# FM_Radio_Simple_Receiver.net
KiCad netlist of a schematic drawn in EAGLE
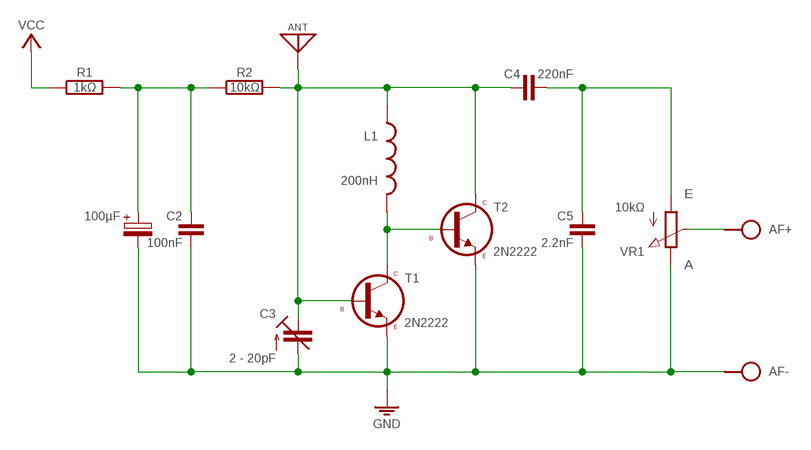
[diagram p0: schematic, sheet 1]

(export (version "E")
  (design (tool "Eeschema 10.0.6"))
  (components
    (comp (ref "100µF")
      (value "CPOLE2,5-5/V")
      (footprint "eagle-import:E2,5-5_V")
      (libsource (lib "eagle-import") (part "CPOLE2,5-5/V"))
    )
    (comp (ref "AF")
      (value "SPAD+-+-")
      (footprint "eagle-import:SPAD+-")
      (libsource (lib "eagle-import") (part "SPAD+-+-"))
    )
    (comp (ref "ANT")
      (value "ANT")
      (footprint "eagle-import:SPAD")
      (libsource (lib "eagle-import") (part "ANT"))
    )
    (comp (ref "BAT")
      (value "VCC_GNDL")
      (footprint "eagle-import:SPAD-+")
      (libsource (lib "eagle-import") (part "VCC_GNDL"))
    )
    (comp (ref "C2")
      (value "100nF")
      (footprint "eagle-import:C050-020X036_V")
      (libsource (lib "eagle-import") (part "C050-020X036/V"))
    )
    (comp (ref "C3")
      (value "2 - 20pF")
      (footprint "eagle-import:TRIM-2222-808")
      (libsource (lib "eagle-import") (part "C-TR-PH20127"))
    )
    (comp (ref "C4")
      (value "220nF")
      (footprint "eagle-import:C050-020X044")
      (libsource (lib "eagle-import") (part "C-H050-020X044"))
    )
    (comp (ref "C5")
      (value "2.2nF")
      (footprint "eagle-import:C050-020X036_V")
      (libsource (lib "eagle-import") (part "C050-020X036/V"))
    )
    (comp (ref "L1")
      (value "200nH")
      (footprint "eagle-import:L-04_7-V")
      (libsource (lib "eagle-import") (part "L04/7-V"))
    )
    (comp (ref "R1")
      (value "1kΩ")
      (footprint "eagle-import:0204_10")
      (libsource (lib "eagle-import") (part "R-H0204/10"))
    )
    (comp (ref "R2")
      (value "10kΩ")
      (footprint "eagle-import:0204_10")
      (libsource (lib "eagle-import") (part "R-H0204/10"))
    )
    (comp (ref "T1")
      (value "2N2222")
      (footprint "eagle-import:TO92-EBC")
      (libsource (lib "eagle-import") (part "2N2222"))
    )
    (comp (ref "T2")
      (value "2N2222")
      (footprint "eagle-import:TO92-EBC")
      (libsource (lib "eagle-import") (part "2N2222"))
    )
    (comp (ref "VR1")
      (value "10kΩ")
      (footprint "eagle-import:POT")
      (libsource (lib "eagle-import") (part "POT"))
    )
  )
  (nets
    (net (code "1") (name "Net-(100µF-Pad+)") (class "Default")
      (node (ref "100µF") (pin "+") (pinfunction "+_+") (pintype "passive"))
      (node (ref "C2") (pin "1") (pinfunction "1_1") (pintype "passive"))
      (node (ref "R1") (pin "2") (pinfunction "2_2") (pintype "passive"))
      (node (ref "R2") (pin "1") (pinfunction "1_1") (pintype "passive"))
    )
    (net (code "2") (name "Net-(AFA-P$1)") (class "Default")
      (node (ref "AF") (pin "2") (pinfunction "P$1_2") (pintype "passive"))
      (node (ref "VR1") (pin "S") (pinfunction "S_S") (pintype "passive"))
    )
    (net (code "3") (name "Net-(AFB-P$1)") (class "Default")
      (node (ref "100µF") (pin "-") (pinfunction "-_-") (pintype "passive"))
      (node (ref "AF") (pin "1") (pinfunction "P$1_1") (pintype "passive"))
      (node (ref "BAT") (pin "1") (pinfunction "GND_1") (pintype "power_in"))
      (node (ref "C2") (pin "2") (pinfunction "2_2") (pintype "passive"))
      (node (ref "C3") (pin "1") (pinfunction "A_1") (pintype "passive"))
      (node (ref "C3") (pin "3") (pinfunction "A_3") (pintype "passive"))
      (node (ref "C5") (pin "2") (pinfunction "2_2") (pintype "passive"))
      (node (ref "T1") (pin "E") (pinfunction "E_E") (pintype "passive"))
      (node (ref "T2") (pin "E") (pinfunction "E_E") (pintype "passive"))
      (node (ref "VR1") (pin "E") (pinfunction "E_E") (pintype "passive"))
    )
    (net (code "4") (name "Net-(BATA-VCC)") (class "Default")
      (node (ref "BAT") (pin "2") (pinfunction "VCC_2") (pintype "power_in"))
      (node (ref "R1") (pin "1") (pinfunction "1_1") (pintype "passive"))
    )
    (net (code "5") (name "Net-(C3-E)") (class "Default")
      (node (ref "ANT") (pin "1") (pinfunction "1_1") (pintype "output"))
      (node (ref "C3") (pin "2") (pinfunction "E_2") (pintype "passive"))
      (node (ref "C4") (pin "1") (pinfunction "1_1") (pintype "passive"))
      (node (ref "L1") (pin "1") (pinfunction "1_1") (pintype "passive"))
      (node (ref "R2") (pin "2") (pinfunction "2_2") (pintype "passive"))
      (node (ref "T1") (pin "B") (pinfunction "B_B") (pintype "passive"))
      (node (ref "T2") (pin "C") (pinfunction "C_C") (pintype "passive"))
    )
    (net (code "6") (name "Net-(C4-Pad2)") (class "Default")
      (node (ref "C4") (pin "2") (pinfunction "2_2") (pintype "passive"))
      (node (ref "C5") (pin "1") (pinfunction "1_1") (pintype "passive"))
      (node (ref "VR1") (pin "A") (pinfunction "A_A") (pintype "passive"))
    )
    (net (code "7") (name "Net-(L1-Pad2)") (class "Default")
      (node (ref "L1") (pin "2") (pinfunction "2_2") (pintype "passive"))
      (node (ref "T1") (pin "C") (pinfunction "C_C") (pintype "passive"))
      (node (ref "T2") (pin "B") (pinfunction "B_B") (pintype "passive"))
    )
  )
)
